# Stick_IMUinator_v1_3.net
KiCad netlist of a schematic drawn in EAGLE
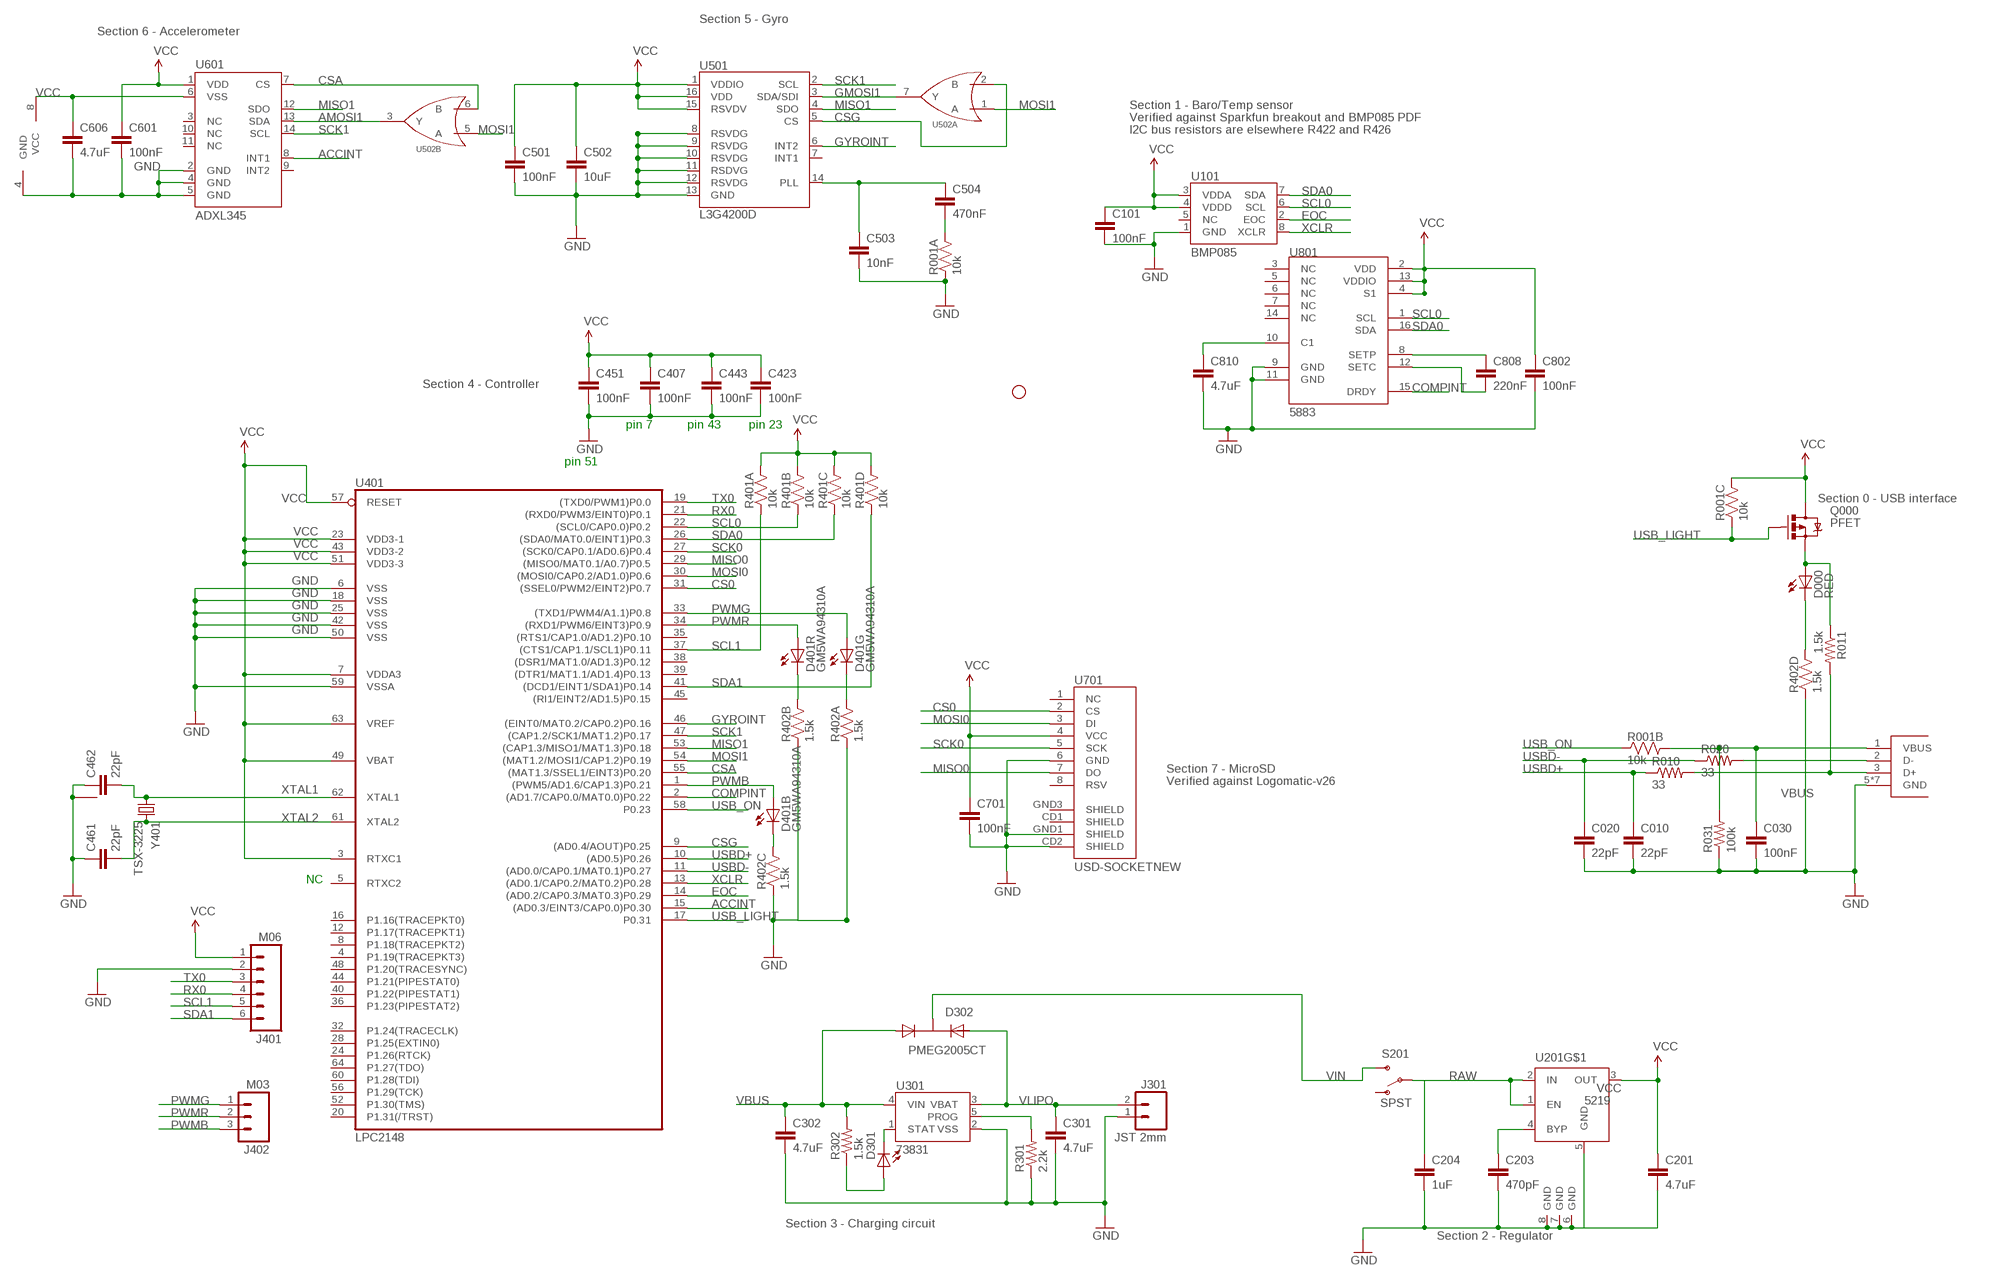
[diagram p0: schematic, sheet 1]

(export (version "E")
  (design (tool "Eeschema 10.0.6"))
  (components
    (comp (ref "C010")
      (value "22pF")
      (footprint "eagle-import:0402-CAP")
      (libsource (lib "eagle-import") (part "CAP0402-CAP"))
    )
    (comp (ref "C020")
      (value "22pF")
      (footprint "eagle-import:0402-CAP")
      (libsource (lib "eagle-import") (part "CAP0402-CAP"))
    )
    (comp (ref "C030")
      (value "100nF")
      (footprint "eagle-import:0402-CAP")
      (libsource (lib "eagle-import") (part "CAP0402-CAP"))
    )
    (comp (ref "C101")
      (value "100nF")
      (footprint "eagle-import:0402-CAP")
      (libsource (lib "eagle-import") (part "CAP0402-CAP"))
    )
    (comp (ref "C201")
      (value "4.7uF")
      (footprint "eagle-import:0402-CAP")
      (libsource (lib "eagle-import") (part "CAP0402-CAP"))
    )
    (comp (ref "C203")
      (value "470pF")
      (footprint "eagle-import:0402-CAP")
      (libsource (lib "eagle-import") (part "CAP0402-CAP"))
    )
    (comp (ref "C204")
      (value "1uF")
      (footprint "eagle-import:0402-CAP")
      (libsource (lib "eagle-import") (part "CAP0402-CAP"))
    )
    (comp (ref "C301")
      (value "4.7uF")
      (footprint "eagle-import:0402-CAP")
      (libsource (lib "eagle-import") (part "CAP0402-CAP"))
    )
    (comp (ref "C302")
      (value "4.7uF")
      (footprint "eagle-import:0402-CAP")
      (libsource (lib "eagle-import") (part "CAP0402-CAP"))
    )
    (comp (ref "C407")
      (value "100nF")
      (footprint "eagle-import:0402-CAP")
      (libsource (lib "eagle-import") (part "CAP0402-CAP"))
    )
    (comp (ref "C423")
      (value "100nF")
      (footprint "eagle-import:0402-CAP")
      (libsource (lib "eagle-import") (part "CAP0402-CAP"))
    )
    (comp (ref "C443")
      (value "100nF")
      (footprint "eagle-import:0402-CAP")
      (libsource (lib "eagle-import") (part "CAP0402-CAP"))
    )
    (comp (ref "C451")
      (value "100nF")
      (footprint "eagle-import:0402-CAP")
      (libsource (lib "eagle-import") (part "CAP0402-CAP"))
    )
    (comp (ref "C461")
      (value "22pF")
      (footprint "eagle-import:0402-CAP")
      (libsource (lib "eagle-import") (part "CAP0402-CAP"))
    )
    (comp (ref "C462")
      (value "22pF")
      (footprint "eagle-import:0402-CAP")
      (libsource (lib "eagle-import") (part "CAP0402-CAP"))
    )
    (comp (ref "C501")
      (value "100nF")
      (footprint "eagle-import:0402-CAP")
      (libsource (lib "eagle-import") (part "CAP0402-CAP"))
    )
    (comp (ref "C502")
      (value "10uF")
      (footprint "eagle-import:0603-CAP")
      (libsource (lib "eagle-import") (part "CAP0603-CAP"))
    )
    (comp (ref "C503")
      (value "10nF")
      (footprint "eagle-import:0402-CAP")
      (libsource (lib "eagle-import") (part "CAP0402-CAP"))
    )
    (comp (ref "C504")
      (value "470nF")
      (footprint "eagle-import:0402-CAP")
      (libsource (lib "eagle-import") (part "CAP0402-CAP"))
    )
    (comp (ref "C601")
      (value "100nF")
      (footprint "eagle-import:0402-CAP")
      (libsource (lib "eagle-import") (part "CAP0402-CAP"))
    )
    (comp (ref "C606")
      (value "4.7uF")
      (footprint "eagle-import:0402-CAP")
      (libsource (lib "eagle-import") (part "CAP0402-CAP"))
    )
    (comp (ref "C701")
      (value "100nF")
      (footprint "eagle-import:0402-CAP")
      (libsource (lib "eagle-import") (part "CAP0402-CAP"))
    )
    (comp (ref "C802")
      (value "100nF")
      (footprint "eagle-import:0402-CAP")
      (libsource (lib "eagle-import") (part "CAP0402-CAP"))
    )
    (comp (ref "C808")
      (value "220nF")
      (footprint "eagle-import:0402-CAP")
      (libsource (lib "eagle-import") (part "CAP0402-CAP"))
    )
    (comp (ref "C810")
      (value "4.7uF")
      (footprint "eagle-import:0402-CAP")
      (libsource (lib "eagle-import") (part "CAP0402-CAP"))
    )
    (comp (ref "D000")
      (value "RED")
      (footprint "eagle-import:LED-0603")
      (libsource (lib "eagle-import") (part "LED0603"))
    )
    (comp (ref "D301")
      (value "RED")
      (footprint "eagle-import:LED-0603")
      (libsource (lib "eagle-import") (part "LED0603"))
    )
    (comp (ref "D302")
      (value "PMEG2005CT")
      (footprint "eagle-import:SOT-23-3")
      (libsource (lib "eagle-import") (part "PMEG2005CT"))
    )
    (comp (ref "D401")
      (value "GM5WA94310A")
      (footprint "eagle-import:GM5WA94310A")
      (libsource (lib "eagle-import") (part "GM5WA94310A"))
    )
    (comp (ref "J301")
      (value "JST 2mm")
      (footprint "eagle-import:JST-2-SMD")
      (libsource (lib "eagle-import") (part "M02-JST-2MM-SMT"))
    )
    (comp (ref "J401")
      (value "M06")
      (footprint "eagle-import:1X06_LOCK")
      (libsource (lib "eagle-import") (part "M06LOCK"))
    )
    (comp (ref "J402")
      (value "M03")
      (footprint "eagle-import:1X03_LOCK")
      (libsource (lib "eagle-import") (part "M03LOCK"))
    )
    (comp (ref "JP1")
      (value "STAND-OFF")
      (footprint "eagle-import:STAND-OFF")
      (libsource (lib "eagle-import") (part "STAND-OFF"))
    )
    (comp (ref "Q000")
      (value "PFET")
      (footprint "eagle-import:SOT23-3")
      (libsource (lib "eagle-import") (part "MOSFET-PCHANNELSMD"))
    )
    (comp (ref "R001")
      (value "10k")
      (footprint "eagle-import:CRA04")
      (libsource (lib "eagle-import") (part "RP404"))
    )
    (comp (ref "R010")
      (value "33")
      (footprint "eagle-import:0402-RES")
      (libsource (lib "eagle-import") (part "RESISTOR0402-RES"))
    )
    (comp (ref "R011")
      (value "1.5k")
      (footprint "eagle-import:0402-RES")
      (libsource (lib "eagle-import") (part "RESISTOR0402-RES"))
    )
    (comp (ref "R020")
      (value "33")
      (footprint "eagle-import:0402-RES")
      (libsource (lib "eagle-import") (part "RESISTOR0402-RES"))
    )
    (comp (ref "R031")
      (value "100k")
      (footprint "eagle-import:0402-RES")
      (libsource (lib "eagle-import") (part "RESISTOR0402-RES"))
    )
    (comp (ref "R301")
      (value "2.2k")
      (footprint "eagle-import:0402-RES")
      (libsource (lib "eagle-import") (part "RESISTOR0402-RES"))
    )
    (comp (ref "R302")
      (value "1.5k")
      (footprint "eagle-import:0402-RES")
      (libsource (lib "eagle-import") (part "RESISTOR0402-RES"))
    )
    (comp (ref "R401")
      (value "10k")
      (footprint "eagle-import:CRA04")
      (libsource (lib "eagle-import") (part "RP404"))
    )
    (comp (ref "R402")
      (value "1.5k")
      (footprint "eagle-import:CRA04")
      (libsource (lib "eagle-import") (part "RP404"))
    )
    (comp (ref "S201")
      (value "SPST")
      (footprint "eagle-import:AYZ0202")
      (libsource (lib "eagle-import") (part "SWITCH-SPSTSMD"))
    )
    (comp (ref "U$1")
      (value "USB_MICROB_JST")
      (footprint "eagle-import:UB-MC5BR3-SD204-4S")
      (libsource (lib "eagle-import") (part "USB_MICROB_JST"))
    )
    (comp (ref "U101")
      (value "BMP085")
      (footprint "eagle-import:BMP085")
      (libsource (lib "eagle-import") (part "BMP085"))
    )
    (comp (ref "U201")
      (value "5219")
      (footprint "eagle-import:MSOP08")
      (libsource (lib "eagle-import") (part "MIC5219FMM"))
    )
    (comp (ref "U301")
      (value "73831")
      (footprint "eagle-import:SOT23-5")
      (libsource (lib "eagle-import") (part "MCP73831"))
    )
    (comp (ref "U401")
      (value "LPC2148")
      (footprint "eagle-import:SQFP-S-10X10-64")
      (libsource (lib "eagle-import") (part "LPC213X"))
    )
    (comp (ref "U501")
      (value "L3G4200D")
      (footprint "eagle-import:LGA16-4X4")
      (libsource (lib "eagle-import") (part "L3G4200D"))
    )
    (comp (ref "U502")
      (value "SN74LVC2G32")
      (footprint "eagle-import:DCU_8")
      (libsource (lib "eagle-import") (part "SN74LVC2G32"))
    )
    (comp (ref "U601")
      (value "ADXL345")
      (footprint "eagle-import:LGA14")
      (libsource (lib "eagle-import") (part "ADXL345"))
    )
    (comp (ref "U701")
      (value "USD-SOCKETNEW")
      (footprint "eagle-import:MICRO-SD-SOCKET-PP")
      (libsource (lib "eagle-import") (part "USD-SOCKETNEW"))
    )
    (comp (ref "U801")
      (value "5883")
      (footprint "eagle-import:16LPCC")
      (libsource (lib "eagle-import") (part "HMC5883LSMD"))
    )
    (comp (ref "Y401")
      (value "TSX-3225")
      (footprint "eagle-import:CRYSTAL_SMD")
      (libsource (lib "eagle-import") (part "TSX-3225"))
    )
  )
  (nets
    (net (code "1") (name "/ACCINT") (class "Default")
      (node (ref "U401") (pin "15") (pinfunction "(AD0.3/EINT3/CAP0.0)P0.30_15") (pintype "bidirectional"))
      (node (ref "U601") (pin "8") (pinfunction "INT1_8") (pintype "bidirectional"))
    )
    (net (code "2") (name "/AMOSI1") (class "Default")
      (node (ref "U502") (pin "3") (pinfunction "Y_3") (pintype "bidirectional"))
      (node (ref "U601") (pin "13") (pinfunction "SDA_13") (pintype "bidirectional"))
    )
    (net (code "3") (name "/COMPINT") (class "Default")
      (node (ref "U401") (pin "2") (pinfunction "(AD1.7/CAP0.0/MAT0.0)P0.22_2") (pintype "bidirectional"))
      (node (ref "U801") (pin "15") (pinfunction "DRDY_15") (pintype "bidirectional"))
    )
    (net (code "4") (name "/CS0") (class "Default")
      (node (ref "U401") (pin "31") (pinfunction "(SSEL0/PWM2/EINT2)P0.7_31") (pintype "bidirectional"))
      (node (ref "U701") (pin "2") (pinfunction "CS_2") (pintype "bidirectional"))
    )
    (net (code "5") (name "/CSA") (class "Default")
      (node (ref "U401") (pin "55") (pinfunction "(MAT1.3/SSEL1/EINT3)P0.20_55") (pintype "bidirectional"))
      (node (ref "U502") (pin "6") (pinfunction "B_6") (pintype "bidirectional"))
      (node (ref "U601") (pin "7") (pinfunction "CS_7") (pintype "bidirectional"))
    )
    (net (code "6") (name "/CSG") (class "Default")
      (node (ref "U401") (pin "9") (pinfunction "(AD0.4/AOUT)P0.25_9") (pintype "bidirectional"))
      (node (ref "U501") (pin "5") (pinfunction "CS_5") (pintype "bidirectional"))
      (node (ref "U502") (pin "2") (pinfunction "B_2") (pintype "bidirectional"))
    )
    (net (code "7") (name "/EOC") (class "Default")
      (node (ref "U101") (pin "2") (pinfunction "EOC_2") (pintype "output"))
      (node (ref "U401") (pin "14") (pinfunction "(AD0.2/CAP0.3/MAT0.3)P0.29_14") (pintype "bidirectional"))
    )
    (net (code "8") (name "/GMOSI1") (class "Default")
      (node (ref "U501") (pin "3") (pinfunction "SDA/SDI_3") (pintype "bidirectional"))
      (node (ref "U502") (pin "7") (pinfunction "Y_7") (pintype "bidirectional"))
    )
    (net (code "9") (name "/GYROINT") (class "Default")
      (node (ref "U401") (pin "46") (pinfunction "(EINT0/MAT0.2/CAP0.2)P0.16_46") (pintype "bidirectional"))
      (node (ref "U501") (pin "6") (pinfunction "INT2_6") (pintype "bidirectional"))
    )
    (net (code "10") (name "/MISO0") (class "Default")
      (node (ref "U401") (pin "29") (pinfunction "(MISO0/MAT0.1/A0.7)P0.5_29") (pintype "bidirectional"))
      (node (ref "U701") (pin "7") (pinfunction "DO_7") (pintype "bidirectional"))
    )
    (net (code "11") (name "/MISO1") (class "Default")
      (node (ref "U401") (pin "53") (pinfunction "(CAP1.3/MISO1/MAT1.3)P0.18_53") (pintype "bidirectional"))
      (node (ref "U501") (pin "4") (pinfunction "SDO_4") (pintype "bidirectional"))
      (node (ref "U601") (pin "12") (pinfunction "SDO_12") (pintype "bidirectional"))
    )
    (net (code "12") (name "/MOSI0") (class "Default")
      (node (ref "U401") (pin "30") (pinfunction "(MOSI0/CAP0.2/AD1.0)P0.6_30") (pintype "bidirectional"))
      (node (ref "U701") (pin "3") (pinfunction "DI_3") (pintype "bidirectional"))
    )
    (net (code "13") (name "/MOSI1") (class "Default")
      (node (ref "U401") (pin "54") (pinfunction "(MAT1.2/MOSI1/CAP1.2)P0.19_54") (pintype "bidirectional"))
      (node (ref "U502") (pin "1") (pinfunction "A_1") (pintype "bidirectional"))
      (node (ref "U502") (pin "5") (pinfunction "A_5") (pintype "bidirectional"))
    )
    (net (code "14") (name "/PWMB") (class "Default")
      (node (ref "D401") (pin "1") (pinfunction "A_1") (pintype "passive"))
      (node (ref "J402") (pin "3") (pinfunction "3_3") (pintype "passive"))
      (node (ref "U401") (pin "1") (pinfunction "(PWM5/AD1.6/CAP1.3)P0.21_1") (pintype "bidirectional"))
    )
    (net (code "15") (name "/PWMG") (class "Default")
      (node (ref "D401") (pin "3") (pinfunction "A_3") (pintype "passive"))
      (node (ref "J402") (pin "1") (pinfunction "1_1") (pintype "passive"))
      (node (ref "U401") (pin "33") (pinfunction "(TXD1/PWM4/A1.1)P0.8_33") (pintype "bidirectional"))
    )
    (net (code "16") (name "/PWMR") (class "Default")
      (node (ref "D401") (pin "2") (pinfunction "A_2") (pintype "passive"))
      (node (ref "J402") (pin "2") (pinfunction "2_2") (pintype "passive"))
      (node (ref "U401") (pin "34") (pinfunction "(RXD1/PWM6/EINT3)P0.9_34") (pintype "bidirectional"))
    )
    (net (code "17") (name "/RAW") (class "Default")
      (node (ref "C204") (pin "1") (pinfunction "1_1") (pintype "passive"))
      (node (ref "S201") (pin "2") (pinfunction "P_2") (pintype "passive"))
      (node (ref "U201") (pin "1") (pinfunction "EN_1") (pintype "input"))
      (node (ref "U201") (pin "2") (pinfunction "IN_2") (pintype "input"))
    )
    (net (code "18") (name "/RX0") (class "Default")
      (node (ref "J401") (pin "4") (pinfunction "4_4") (pintype "passive"))
      (node (ref "U401") (pin "21") (pinfunction "(RXD0/PWM3/EINT0)P0.1_21") (pintype "bidirectional"))
    )
    (net (code "19") (name "/SCK0") (class "Default")
      (node (ref "U401") (pin "27") (pinfunction "(SCK0/CAP0.1/AD0.6)P0.4_27") (pintype "bidirectional"))
      (node (ref "U701") (pin "5") (pinfunction "SCK_5") (pintype "bidirectional"))
    )
    (net (code "20") (name "/SCK1") (class "Default")
      (node (ref "U401") (pin "47") (pinfunction "(CAP1.2/SCK1/MAT1.2)P0.17_47") (pintype "bidirectional"))
      (node (ref "U501") (pin "2") (pinfunction "SCL_2") (pintype "bidirectional"))
      (node (ref "U601") (pin "14") (pinfunction "SCL_14") (pintype "bidirectional"))
    )
    (net (code "21") (name "/SCL0") (class "Default")
      (node (ref "R401") (pin "2") (pinfunction "1_2") (pintype "passive"))
      (node (ref "U101") (pin "6") (pinfunction "SCL_6") (pintype "input"))
      (node (ref "U401") (pin "22") (pinfunction "(SCL0/CAP0.0)P0.2_22") (pintype "bidirectional"))
      (node (ref "U801") (pin "1") (pinfunction "SCL_1") (pintype "bidirectional"))
    )
    (net (code "22") (name "/SCL1") (class "Default")
      (node (ref "J401") (pin "5") (pinfunction "5_5") (pintype "passive"))
      (node (ref "R401") (pin "1") (pinfunction "1_1") (pintype "passive"))
      (node (ref "U401") (pin "37") (pinfunction "(CTS1/CAP1.1/SCL1)P0.11_37") (pintype "bidirectional"))
    )
    (net (code "23") (name "/SDA0") (class "Default")
      (node (ref "R401") (pin "3") (pinfunction "1_3") (pintype "passive"))
      (node (ref "U101") (pin "7") (pinfunction "SDA_7") (pintype "bidirectional"))
      (node (ref "U401") (pin "26") (pinfunction "(SDA0/MAT0.0/EINT1)P0.3_26") (pintype "bidirectional"))
      (node (ref "U801") (pin "16") (pinfunction "SDA_16") (pintype "bidirectional"))
    )
    (net (code "24") (name "/SDA1") (class "Default")
      (node (ref "J401") (pin "6") (pinfunction "6_6") (pintype "passive"))
      (node (ref "R401") (pin "4") (pinfunction "1_4") (pintype "passive"))
      (node (ref "U401") (pin "41") (pinfunction "(DCD1/EINT1/SDA1)P0.14_41") (pintype "bidirectional"))
    )
    (net (code "25") (name "/TX0") (class "Default")
      (node (ref "J401") (pin "3") (pinfunction "3_3") (pintype "passive"))
      (node (ref "U401") (pin "19") (pinfunction "(TXD0/PWM1)P0.0_19") (pintype "bidirectional"))
    )
    (net (code "26") (name "/USBD+") (class "Default")
      (node (ref "C010") (pin "1") (pinfunction "1_1") (pintype "passive"))
      (node (ref "R010") (pin "1") (pinfunction "1_1") (pintype "passive"))
      (node (ref "U401") (pin "10") (pinfunction "(AD0.5)P0.26_10") (pintype "bidirectional"))
    )
    (net (code "27") (name "/USBD-") (class "Default")
      (node (ref "C020") (pin "1") (pinfunction "1_1") (pintype "passive"))
      (node (ref "R020") (pin "1") (pinfunction "1_1") (pintype "passive"))
      (node (ref "U401") (pin "11") (pinfunction "(AD0.0/CAP0.1/MAT0.1)P0.27_11") (pintype "bidirectional"))
    )
    (net (code "28") (name "/USB_LIGHT") (class "Default")
      (node (ref "Q000") (pin "1") (pinfunction "G_1") (pintype "passive"))
      (node (ref "R001") (pin "3") (pinfunction "1_3") (pintype "passive"))
      (node (ref "U401") (pin "17") (pinfunction "P0.31_17") (pintype "output"))
    )
    (net (code "29") (name "/USB_ON") (class "Default")
      (node (ref "R001") (pin "2") (pinfunction "1_2") (pintype "passive"))
      (node (ref "U401") (pin "58") (pinfunction "P0.23_58") (pintype "bidirectional"))
    )
    (net (code "30") (name "/VBUS") (class "Default")
      (node (ref "C030") (pin "1") (pinfunction "1_1") (pintype "passive"))
      (node (ref "C302") (pin "1") (pinfunction "1_1") (pintype "passive"))
      (node (ref "D302") (pin "1") (pinfunction "A1_1") (pintype "passive"))
      (node (ref "R001") (pin "7") (pinfunction "2_7") (pintype "passive"))
      (node (ref "R031") (pin "2") (pinfunction "2_2") (pintype "passive"))
      (node (ref "R302") (pin "2") (pinfunction "2_2") (pintype "passive"))
      (node (ref "U$1") (pin "1") (pinfunction "VBUS_1") (pintype "bidirectional"))
      (node (ref "U301") (pin "4") (pinfunction "VIN_4") (pintype "power_in"))
    )
    (net (code "31") (name "/VIN") (class "Default")
      (node (ref "D302") (pin "3") (pinfunction "K_3") (pintype "passive"))
      (node (ref "S201") (pin "3") (pinfunction "S_3") (pintype "passive"))
    )
    (net (code "32") (name "/VLIPO") (class "Default")
      (node (ref "C301") (pin "1") (pinfunction "1_1") (pintype "passive"))
      (node (ref "D302") (pin "2") (pinfunction "A2_2") (pintype "passive"))
      (node (ref "J301") (pin "2") (pinfunction "2_2") (pintype "passive"))
      (node (ref "U301") (pin "3") (pinfunction "VBAT_3") (pintype "power_in"))
    )
    (net (code "33") (name "/XCLR") (class "Default")
      (node (ref "U101") (pin "8") (pinfunction "XCLR_8") (pintype "input"))
      (node (ref "U401") (pin "13") (pinfunction "(AD0.1/CAP0.2/MAT0.2)P0.28_13") (pintype "bidirectional"))
    )
    (net (code "34") (name "/XTAL1") (class "Default")
      (node (ref "C462") (pin "2") (pinfunction "2_2") (pintype "passive"))
      (node (ref "U401") (pin "62") (pinfunction "XTAL1_62") (pintype "input"))
      (node (ref "Y401") (pin "1") (pinfunction "1_1") (pintype "passive"))
    )
    (net (code "35") (name "/XTAL2") (class "Default")
      (node (ref "C461") (pin "2") (pinfunction "2_2") (pintype "passive"))
      (node (ref "U401") (pin "61") (pinfunction "XTAL2_61") (pintype "output"))
      (node (ref "Y401") (pin "3") (pinfunction "2_3") (pintype "passive"))
    )
    (net (code "36") (name "GND") (class "Default")
      (node (ref "C010") (pin "2") (pinfunction "2_2") (pintype "passive"))
      (node (ref "C020") (pin "2") (pinfunction "2_2") (pintype "passive"))
      (node (ref "C030") (pin "2") (pinfunction "2_2") (pintype "passive"))
      (node (ref "C101") (pin "2") (pinfunction "2_2") (pintype "passive"))
      (node (ref "C201") (pin "2") (pinfunction "2_2") (pintype "passive"))
      (node (ref "C203") (pin "2") (pinfunction "2_2") (pintype "passive"))
      (node (ref "C204") (pin "2") (pinfunction "2_2") (pintype "passive"))
      (node (ref "C301") (pin "2") (pinfunction "2_2") (pintype "passive"))
      (node (ref "C302") (pin "2") (pinfunction "2_2") (pintype "passive"))
      (node (ref "C407") (pin "2") (pinfunction "2_2") (pintype "passive"))
      (node (ref "C423") (pin "2") (pinfunction "2_2") (pintype "passive"))
      (node (ref "C443") (pin "2") (pinfunction "2_2") (pintype "passive"))
      (node (ref "C451") (pin "2") (pinfunction "2_2") (pintype "passive"))
      (node (ref "C461") (pin "1") (pinfunction "1_1") (pintype "passive"))
      (node (ref "C462") (pin "1") (pinfunction "1_1") (pintype "passive"))
      (node (ref "C501") (pin "2") (pinfunction "2_2") (pintype "passive"))
      (node (ref "C502") (pin "2") (pinfunction "2_2") (pintype "passive"))
      (node (ref "C503") (pin "2") (pinfunction "2_2") (pintype "passive"))
      (node (ref "C601") (pin "2") (pinfunction "2_2") (pintype "passive"))
      (node (ref "C606") (pin "2") (pinfunction "2_2") (pintype "passive"))
      (node (ref "C701") (pin "2") (pinfunction "2_2") (pintype "passive"))
      (node (ref "C802") (pin "2") (pinfunction "2_2") (pintype "passive"))
      (node (ref "C810") (pin "2") (pinfunction "2_2") (pintype "passive"))
      (node (ref "J301") (pin "1") (pinfunction "1_1") (pintype "passive"))
      (node (ref "J401") (pin "2") (pinfunction "2_2") (pintype "passive"))
      (node (ref "R001") (pin "1") (pinfunction "1_1") (pintype "passive"))
      (node (ref "R031") (pin "1") (pinfunction "1_1") (pintype "passive"))
      (node (ref "R301") (pin "1") (pinfunction "1_1") (pintype "passive"))
      (node (ref "R402") (pin "1") (pinfunction "1_1") (pintype "passive"))
      (node (ref "R402") (pin "2") (pinfunction "1_2") (pintype "passive"))
      (node (ref "R402") (pin "3") (pinfunction "1_3") (pintype "passive"))
      (node (ref "R402") (pin "4") (pinfunction "1_4") (pintype "passive"))
      (node (ref "U$1") (pin "5") (pinfunction "GND_5") (pintype "bidirectional"))
      (node (ref "U$1") (pin "P$10") (pinfunction "GND_P$10") (pintype "bidirectional"))
      (node (ref "U$1") (pin "P$11") (pinfunction "GND_P$11") (pintype "bidirectional"))
      (node (ref "U$1") (pin "P$6") (pinfunction "GND_P$6") (pintype "bidirectional"))
      (node (ref "U$1") (pin "P$7") (pinfunction "GND_P$7") (pintype "bidirectional"))
      (node (ref "U$1") (pin "P$8") (pinfunction "GND_P$8") (pintype "bidirectional"))
      (node (ref "U$1") (pin "P$9") (pinfunction "GND_P$9") (pintype "bidirectional"))
      (node (ref "U101") (pin "1") (pinfunction "GND_1") (pintype "power_in"))
      (node (ref "U201") (pin "5") (pinfunction "GND_5") (pintype "power_in"))
      (node (ref "U201") (pin "6") (pinfunction "GND_6") (pintype "power_in"))
      (node (ref "U201") (pin "7") (pinfunction "GND_7") (pintype "power_in"))
      (node (ref "U201") (pin "8") (pinfunction "GND_8") (pintype "power_in"))
      (node (ref "U301") (pin "2") (pinfunction "VSS_2") (pintype "power_in"))
      (node (ref "U401") (pin "18") (pinfunction "VSS_18") (pintype "power_in"))
      (node (ref "U401") (pin "25") (pinfunction "VSS_25") (pintype "power_in"))
      (node (ref "U401") (pin "42") (pinfunction "VSS_42") (pintype "power_in"))
      (node (ref "U401") (pin "50") (pinfunction "VSS_50") (pintype "power_in"))
      (node (ref "U401") (pin "59") (pinfunction "VSSA_59") (pintype "power_in"))
      (node (ref "U401") (pin "6") (pinfunction "VSS_6") (pintype "power_in"))
      (node (ref "U501") (pin "10") (pinfunction "RSVDG_10") (pintype "bidirectional"))
      (node (ref "U501") (pin "11") (pinfunction "RSDVG_11") (pintype "bidirectional"))
      (node (ref "U501") (pin "12") (pinfunction "RSVDG_12") (pintype "bidirectional"))
      (node (ref "U501") (pin "13") (pinfunction "GND_13") (pintype "bidirectional"))
      (node (ref "U501") (pin "8") (pinfunction "RSVDG_8") (pintype "bidirectional"))
      (node (ref "U501") (pin "9") (pinfunction "RSVDG_9") (pintype "bidirectional"))
      (node (ref "U502") (pin "4") (pinfunction "GND_4") (pintype "bidirectional"))
      (node (ref "U601") (pin "2") (pinfunction "GND_2") (pintype "bidirectional"))
      (node (ref "U601") (pin "4") (pinfunction "GND_4") (pintype "bidirectional"))
      (node (ref "U601") (pin "5") (pinfunction "GND_5") (pintype "bidirectional"))
      (node (ref "U701") (pin "6") (pinfunction "GND_6") (pintype "bidirectional"))
      (node (ref "U701") (pin "CD2") (pinfunction "SHIELD_CD2") (pintype "bidirectional"))
      (node (ref "U701") (pin "GND1") (pinfunction "SHIELD_GND1") (pintype "bidirectional"))
      (node (ref "U801") (pin "11") (pinfunction "GND_11") (pintype "bidirectional"))
      (node (ref "U801") (pin "9") (pinfunction "GND_9") (pintype "bidirectional"))
      (node (ref "Y401") (pin "2") (pinfunction "1_2") (pintype "bidirectional"))
      (node (ref "Y401") (pin "4") (pinfunction "1_4") (pintype "bidirectional"))
    )
    (net (code "37") (name "Net-(D301-PadA)") (class "Default")
      (node (ref "D301") (pin "A") (pinfunction "A_A") (pintype "passive"))
      (node (ref "R302") (pin "1") (pinfunction "1_1") (pintype "passive"))
    )
    (net (code "38") (name "Net-(D401A-C)") (class "Default")
      (node (ref "D401") (pin "6") (pinfunction "C_6") (pintype "passive"))
      (node (ref "R402") (pin "6") (pinfunction "2_6") (pintype "passive"))
    )
    (net (code "39") (name "Net-(D401B-C)") (class "Default")
      (node (ref "D401") (pin "4") (pinfunction "C_4") (pintype "passive"))
      (node (ref "R402") (pin "8") (pinfunction "2_8") (pintype "passive"))
    )
    (net (code "40") (name "Net-(D401C-C)") (class "Default")
      (node (ref "D401") (pin "5") (pinfunction "C_5") (pintype "passive"))
      (node (ref "R402") (pin "7") (pinfunction "2_7") (pintype "passive"))
    )
    (net (code "41") (name "Net-(Q000-S)") (class "Default")
      (node (ref "D000") (pin "A") (pinfunction "A_A") (pintype "passive"))
      (node (ref "Q000") (pin "2") (pinfunction "S_2") (pintype "passive"))
      (node (ref "R011") (pin "1") (pinfunction "1_1") (pintype "passive"))
    )
    (net (code "42") (name "Net-(R001A-2)") (class "Default")
      (node (ref "C504") (pin "2") (pinfunction "2_2") (pintype "passive"))
      (node (ref "R001") (pin "8") (pinfunction "2_8") (pintype "passive"))
    )
    (net (code "43") (name "Net-(R402D-2)") (class "Default")
      (node (ref "D000") (pin "C") (pinfunction "C_C") (pintype "passive"))
      (node (ref "R402") (pin "5") (pinfunction "2_5") (pintype "passive"))
    )
    (net (code "44") (name "Net-(U$1-D+)") (class "Default")
      (node (ref "R010") (pin "2") (pinfunction "2_2") (pintype "passive"))
      (node (ref "R011") (pin "2") (pinfunction "2_2") (pintype "passive"))
      (node (ref "U$1") (pin "3") (pinfunction "D+_3") (pintype "bidirectional"))
    )
    (net (code "45") (name "Net-(U$1-D-)") (class "Default")
      (node (ref "R020") (pin "2") (pinfunction "2_2") (pintype "passive"))
      (node (ref "U$1") (pin "2") (pinfunction "D-_2") (pintype "bidirectional"))
    )
    (net (code "46") (name "Net-(U201A-BYP)") (class "Default")
      (node (ref "C203") (pin "1") (pinfunction "1_1") (pintype "passive"))
      (node (ref "U201") (pin "4") (pinfunction "BYP_4") (pintype "passive"))
    )
    (net (code "47") (name "Net-(U301-PROG)") (class "Default")
      (node (ref "R301") (pin "2") (pinfunction "2_2") (pintype "passive"))
      (node (ref "U301") (pin "5") (pinfunction "PROG_5") (pintype "input"))
    )
    (net (code "48") (name "Net-(U301-STAT)") (class "Default")
      (node (ref "D301") (pin "C") (pinfunction "C_C") (pintype "passive"))
      (node (ref "U301") (pin "1") (pinfunction "STAT_1") (pintype "output"))
    )
    (net (code "49") (name "Net-(U501-PLL)") (class "Default")
      (node (ref "C503") (pin "1") (pinfunction "1_1") (pintype "passive"))
      (node (ref "C504") (pin "1") (pinfunction "1_1") (pintype "passive"))
      (node (ref "U501") (pin "14") (pinfunction "PLL_14") (pintype "bidirectional"))
    )
    (net (code "50") (name "Net-(U801-C1)") (class "Default")
      (node (ref "C810") (pin "1") (pinfunction "1_1") (pintype "passive"))
      (node (ref "U801") (pin "10") (pinfunction "C1_10") (pintype "bidirectional"))
    )
    (net (code "51") (name "Net-(U801-SETC)") (class "Default")
      (node (ref "C808") (pin "2") (pinfunction "2_2") (pintype "passive"))
      (node (ref "U801") (pin "12") (pinfunction "SETC_12") (pintype "bidirectional"))
    )
    (net (code "52") (name "Net-(U801-SETP)") (class "Default")
      (node (ref "C808") (pin "1") (pinfunction "1_1") (pintype "passive"))
      (node (ref "U801") (pin "8") (pinfunction "SETP_8") (pintype "bidirectional"))
    )
    (net (code "53") (name "VCC") (class "Default")
      (node (ref "C101") (pin "1") (pinfunction "1_1") (pintype "passive"))
      (node (ref "C201") (pin "1") (pinfunction "1_1") (pintype "passive"))
      (node (ref "C407") (pin "1") (pinfunction "1_1") (pintype "passive"))
      (node (ref "C423") (pin "1") (pinfunction "1_1") (pintype "passive"))
      (node (ref "C443") (pin "1") (pinfunction "1_1") (pintype "passive"))
      (node (ref "C451") (pin "1") (pinfunction "1_1") (pintype "passive"))
      (node (ref "C501") (pin "1") (pinfunction "1_1") (pintype "passive"))
      (node (ref "C502") (pin "1") (pinfunction "1_1") (pintype "passive"))
      (node (ref "C601") (pin "1") (pinfunction "1_1") (pintype "passive"))
      (node (ref "C606") (pin "1") (pinfunction "1_1") (pintype "passive"))
      (node (ref "C701") (pin "1") (pinfunction "1_1") (pintype "passive"))
      (node (ref "C802") (pin "1") (pinfunction "1_1") (pintype "passive"))
      (node (ref "J401") (pin "1") (pinfunction "1_1") (pintype "passive"))
      (node (ref "Q000") (pin "3") (pinfunction "D_3") (pintype "passive"))
      (node (ref "R001") (pin "6") (pinfunction "2_6") (pintype "passive"))
      (node (ref "R401") (pin "5") (pinfunction "2_5") (pintype "passive"))
      (node (ref "R401") (pin "6") (pinfunction "2_6") (pintype "passive"))
      (node (ref "R401") (pin "7") (pinfunction "2_7") (pintype "passive"))
      (node (ref "R401") (pin "8") (pinfunction "2_8") (pintype "passive"))
      (node (ref "U101") (pin "3") (pinfunction "VDDA_3") (pintype "power_in"))
      (node (ref "U101") (pin "4") (pinfunction "VDDD_4") (pintype "power_in"))
      (node (ref "U201") (pin "3") (pinfunction "OUT_3") (pintype "output"))
      (node (ref "U401") (pin "23") (pinfunction "VDD3-1_23") (pintype "power_in"))
      (node (ref "U401") (pin "3") (pinfunction "RTXC1_3") (pintype "input"))
      (node (ref "U401") (pin "43") (pinfunction "VDD3-2_43") (pintype "power_in"))
      (node (ref "U401") (pin "49") (pinfunction "VBAT_49") (pintype "power_in"))
      (node (ref "U401") (pin "51") (pinfunction "VDD3-3_51") (pintype "power_in"))
      (node (ref "U401") (pin "57") (pinfunction "RESET_57") (pintype "input"))
      (node (ref "U401") (pin "63") (pinfunction "VREF_63") (pintype "input"))
      (node (ref "U401") (pin "7") (pinfunction "VDDA3_7") (pintype "power_in"))
      (node (ref "U501") (pin "1") (pinfunction "VDDIO_1") (pintype "bidirectional"))
      (node (ref "U501") (pin "15") (pinfunction "RSVDV_15") (pintype "bidirectional"))
      (node (ref "U501") (pin "16") (pinfunction "VDD_16") (pintype "bidirectional"))
      (node (ref "U502") (pin "8") (pinfunction "VCC_8") (pintype "bidirectional"))
      (node (ref "U601") (pin "1") (pinfunction "VDD_1") (pintype "bidirectional"))
      (node (ref "U601") (pin "6") (pinfunction "VSS_6") (pintype "bidirectional"))
      (node (ref "U701") (pin "4") (pinfunction "VCC_4") (pintype "bidirectional"))
      (node (ref "U801") (pin "13") (pinfunction "VDDIO_13") (pintype "bidirectional"))
      (node (ref "U801") (pin "2") (pinfunction "VDD_2") (pintype "bidirectional"))
      (node (ref "U801") (pin "4") (pinfunction "S1_4") (pintype "bidirectional"))
    )
    (net (code "54") (name "unconnected-(S201-O-Pad1)") (class "Default")
      (node (ref "S201") (pin "1") (pinfunction "O_1") (pintype "passive"))
    )
    (net (code "55") (name "unconnected-(U101-NC-Pad5)") (class "Default")
      (node (ref "U101") (pin "5") (pinfunction "NC_5") (pintype "bidirectional"))
    )
    (net (code "56") (name "unconnected-(U401-(DSR1{slash}MAT1.0{slash}AD1.3)P0.12-Pad38)") (class "Default")
      (node (ref "U401") (pin "38") (pinfunction "(DSR1/MAT1.0/AD1.3)P0.12_38") (pintype "bidirectional"))
    )
    (net (code "57") (name "unconnected-(U401-(DTR1{slash}MAT1.1{slash}AD1.4)P0.13-Pad39)") (class "Default")
      (node (ref "U401") (pin "39") (pinfunction "(DTR1/MAT1.1/AD1.4)P0.13_39") (pintype "bidirectional"))
    )
    (net (code "58") (name "unconnected-(U401-(RI1{slash}EINT2{slash}AD1.5)P0.15-Pad45)") (class "Default")
      (node (ref "U401") (pin "45") (pinfunction "(RI1/EINT2/AD1.5)P0.15_45") (pintype "bidirectional"))
    )
    (net (code "59") (name "unconnected-(U401-(RTS1{slash}CAP1.0{slash}AD1.2)P0.10-Pad35)") (class "Default")
      (node (ref "U401") (pin "35") (pinfunction "(RTS1/CAP1.0/AD1.2)P0.10_35") (pintype "bidirectional"))
    )
    (net (code "60") (name "unconnected-(U401-P1.16(TRACEPKT0)-Pad16)") (class "Default")
      (node (ref "U401") (pin "16") (pinfunction "P1.16(TRACEPKT0)_16") (pintype "bidirectional"))
    )
    (net (code "61") (name "unconnected-(U401-P1.17(TRACEPKT1)-Pad12)") (class "Default")
      (node (ref "U401") (pin "12") (pinfunction "P1.17(TRACEPKT1)_12") (pintype "bidirectional"))
    )
    (net (code "62") (name "unconnected-(U401-P1.18(TRACEPKT2)-Pad8)") (class "Default")
      (node (ref "U401") (pin "8") (pinfunction "P1.18(TRACEPKT2)_8") (pintype "bidirectional"))
    )
    (net (code "63") (name "unconnected-(U401-P1.19(TRACEPKT3)-Pad4)") (class "Default")
      (node (ref "U401") (pin "4") (pinfunction "P1.19(TRACEPKT3)_4") (pintype "bidirectional"))
    )
    (net (code "64") (name "unconnected-(U401-P1.20(TRACESYNC)-Pad48)") (class "Default")
      (node (ref "U401") (pin "48") (pinfunction "P1.20(TRACESYNC)_48") (pintype "bidirectional"))
    )
    (net (code "65") (name "unconnected-(U401-P1.21(PIPESTAT0)-Pad44)") (class "Default")
      (node (ref "U401") (pin "44") (pinfunction "P1.21(PIPESTAT0)_44") (pintype "bidirectional"))
    )
    (net (code "66") (name "unconnected-(U401-P1.22(PIPESTAT1)-Pad40)") (class "Default")
      (node (ref "U401") (pin "40") (pinfunction "P1.22(PIPESTAT1)_40") (pintype "bidirectional"))
    )
    (net (code "67") (name "unconnected-(U401-P1.23(PIPESTAT2)-Pad36)") (class "Default")
      (node (ref "U401") (pin "36") (pinfunction "P1.23(PIPESTAT2)_36") (pintype "bidirectional"))
    )
    (net (code "68") (name "unconnected-(U401-P1.24(TRACECLK)-Pad32)") (class "Default")
      (node (ref "U401") (pin "32") (pinfunction "P1.24(TRACECLK)_32") (pintype "bidirectional"))
    )
    (net (code "69") (name "unconnected-(U401-P1.25(EXTIN0)-Pad28)") (class "Default")
      (node (ref "U401") (pin "28") (pinfunction "P1.25(EXTIN0)_28") (pintype "bidirectional"))
    )
    (net (code "70") (name "unconnected-(U401-P1.26(RTCK)-Pad24)") (class "Default")
      (node (ref "U401") (pin "24") (pinfunction "P1.26(RTCK)_24") (pintype "bidirectional"))
    )
    (net (code "71") (name "unconnected-(U401-P1.27(TDO)-Pad64)") (class "Default")
      (node (ref "U401") (pin "64") (pinfunction "P1.27(TDO)_64") (pintype "bidirectional"))
    )
    (net (code "72") (name "unconnected-(U401-P1.28(TDI)-Pad60)") (class "Default")
      (node (ref "U401") (pin "60") (pinfunction "P1.28(TDI)_60") (pintype "bidirectional"))
    )
    (net (code "73") (name "unconnected-(U401-P1.29(TCK)-Pad56)") (class "Default")
      (node (ref "U401") (pin "56") (pinfunction "P1.29(TCK)_56") (pintype "bidirectional"))
    )
    (net (code "74") (name "unconnected-(U401-P1.30(TMS)-Pad52)") (class "Default")
      (node (ref "U401") (pin "52") (pinfunction "P1.30(TMS)_52") (pintype "bidirectional"))
    )
    (net (code "75") (name "unconnected-(U401-P1.31({slash}TRST)-Pad20)") (class "Default")
      (node (ref "U401") (pin "20") (pinfunction "P1.31(/TRST)_20") (pintype "bidirectional"))
    )
    (net (code "76") (name "unconnected-(U401-RTXC2-Pad5)") (class "Default")
      (node (ref "U401") (pin "5") (pinfunction "RTXC2_5") (pintype "output"))
    )
    (net (code "77") (name "unconnected-(U501-INT1-Pad7)") (class "Default")
      (node (ref "U501") (pin "7") (pinfunction "INT1_7") (pintype "bidirectional"))
    )
    (net (code "78") (name "unconnected-(U601-INT2-Pad9)") (class "Default")
      (node (ref "U601") (pin "9") (pinfunction "INT2_9") (pintype "bidirectional"))
    )
    (net (code "79") (name "unconnected-(U601-NC-Pad3)") (class "Default")
      (node (ref "U601") (pin "3") (pinfunction "NC_3") (pintype "bidirectional"))
    )
    (net (code "80") (name "unconnected-(U601-NC-Pad10)") (class "Default")
      (node (ref "U601") (pin "10") (pinfunction "NC_10") (pintype "bidirectional"))
    )
    (net (code "81") (name "unconnected-(U601-NC-Pad11)") (class "Default")
      (node (ref "U601") (pin "11") (pinfunction "NC_11") (pintype "bidirectional"))
    )
    (net (code "82") (name "unconnected-(U701-NC-Pad1)") (class "Default")
      (node (ref "U701") (pin "1") (pinfunction "NC_1") (pintype "bidirectional"))
    )
    (net (code "83") (name "unconnected-(U701-RSV-Pad8)") (class "Default")
      (node (ref "U701") (pin "8") (pinfunction "RSV_8") (pintype "bidirectional"))
    )
    (net (code "84") (name "unconnected-(U701-SHIELD-PadCD1)") (class "Default")
      (node (ref "U701") (pin "CD1") (pinfunction "SHIELD_CD1") (pintype "bidirectional"))
    )
    (net (code "85") (name "unconnected-(U701-SHIELD-PadGND3)") (class "Default")
      (node (ref "U701") (pin "GND3") (pinfunction "SHIELD_GND3") (pintype "bidirectional"))
    )
    (net (code "86") (name "unconnected-(U801-NC-Pad3)") (class "Default")
      (node (ref "U801") (pin "3") (pinfunction "NC_3") (pintype "bidirectional"))
    )
    (net (code "87") (name "unconnected-(U801-NC-Pad5)") (class "Default")
      (node (ref "U801") (pin "5") (pinfunction "NC_5") (pintype "bidirectional"))
    )
    (net (code "88") (name "unconnected-(U801-NC-Pad6)") (class "Default")
      (node (ref "U801") (pin "6") (pinfunction "NC_6") (pintype "bidirectional"))
    )
    (net (code "89") (name "unconnected-(U801-NC-Pad7)") (class "Default")
      (node (ref "U801") (pin "7") (pinfunction "NC_7") (pintype "bidirectional"))
    )
    (net (code "90") (name "unconnected-(U801-NC-Pad14)") (class "Default")
      (node (ref "U801") (pin "14") (pinfunction "NC_14") (pintype "bidirectional"))
    )
  )
)
